# design.net
KiCad netlist of a schematic drawn in Altium Designer
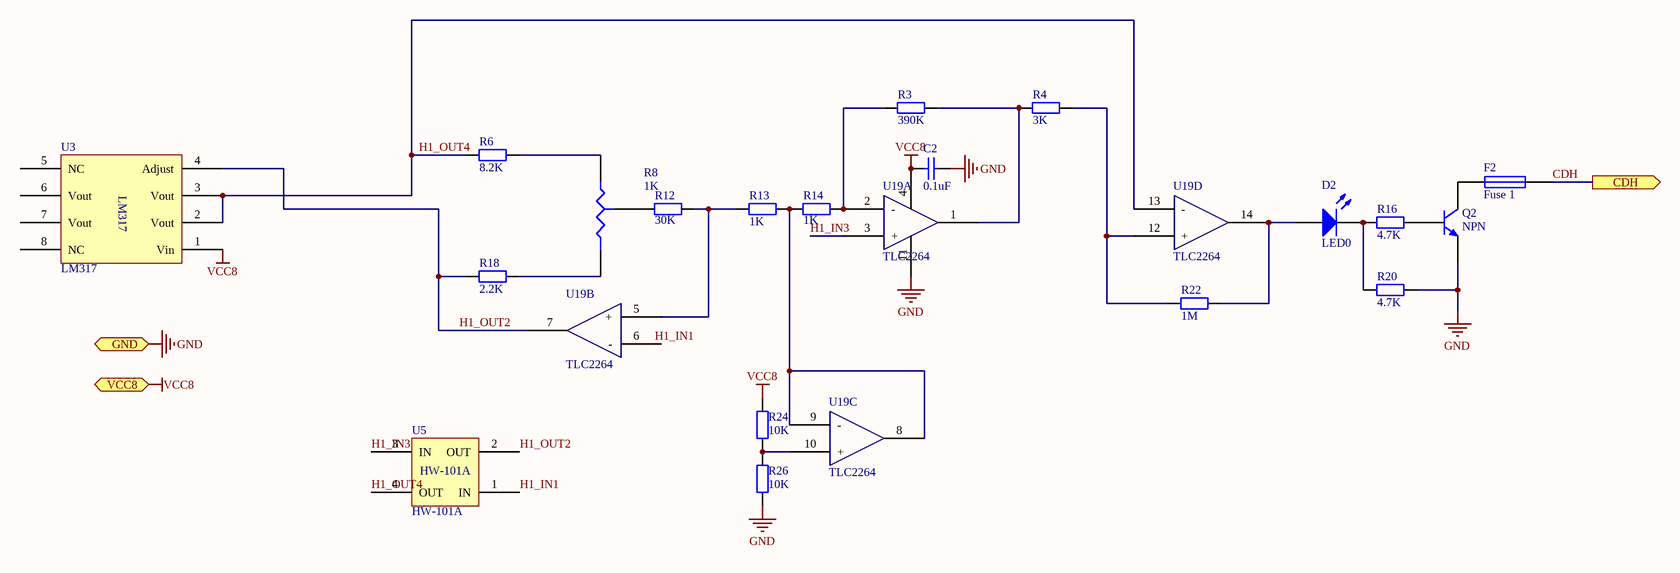
[diagram p0: 单路.SchDoc]

(export (version "E")
  (design (tool "Eeschema 10.0.6"))
  (components
    (comp (ref "C2")
      (value "0.1uF")
      (footprint "C0805")
      (description "Capacitor (Semiconductor SIM Model)")
      (fields (field (name "Comment") "Cap Semi") (field (name "PUBLISHER") "Altium Limited"))
      (libsource (lib "Miscellaneous Devices") (part "Cap Semi"))
    )
    (comp (ref "D2")
      (value "LED0")
      (footprint "LED1")
      (description "Typical INFRARED GaAs LED")
      (fields (field (name "PUBLISHER") "Altium Limited"))
      (libsource (lib "Miscellaneous Devices") (part "LED0"))
    )
    (comp (ref "F2")
      (value "Fuse 1")
      (footprint "1206")
      (description "Fuse")
      (fields (field (name "PUBLISHER") "Altium Limited"))
      (libsource (lib "Miscellaneous Devices") (part "Fuse 1"))
    )
    (comp (ref "Q2")
      (value "NPN")
      (footprint "SOT-23")
      (description "NPN Bipolar Transistor")
      (fields (field (name "PUBLISHER") "Altium Limited"))
      (libsource (lib "Miscellaneous Devices") (part "NPN"))
    )
    (comp (ref "R3")
      (value "390K")
      (footprint "0805")
      (description "Resistor")
      (fields (field (name "Comment") "Res2") (field (name "PUBLISHER") "Altium Limited"))
      (libsource (lib "Miscellaneous Devices") (part "Res2"))
    )
    (comp (ref "R4")
      (value "3K")
      (footprint "0805")
      (description "Resistor")
      (fields (field (name "Comment") "Res2") (field (name "PUBLISHER") "Altium Limited"))
      (libsource (lib "Miscellaneous Devices") (part "Res2"))
    )
    (comp (ref "R6")
      (value "8.2K")
      (footprint "0805")
      (description "Resistor")
      (fields (field (name "Comment") "Res2") (field (name "PUBLISHER") "Altium Limited"))
      (libsource (lib "Miscellaneous Devices") (part "Res2"))
    )
    (comp (ref "R8")
      (value "1K")
      (footprint "3224W")
      (description "Tapped Resistor")
      (fields (field (name "Comment") "Res Tap") (field (name "PUBLISHER") "Altium Limited"))
      (libsource (lib "Miscellaneous Devices") (part "Res Tap"))
    )
    (comp (ref "R12")
      (value "30K")
      (footprint "0805")
      (description "Resistor")
      (fields (field (name "Comment") "Res2") (field (name "PUBLISHER") "Altium Limited"))
      (libsource (lib "Miscellaneous Devices") (part "Res2"))
    )
    (comp (ref "R13")
      (value "1K")
      (footprint "0805")
      (description "Resistor")
      (fields (field (name "Comment") "Res2") (field (name "PUBLISHER") "Altium Limited"))
      (libsource (lib "Miscellaneous Devices") (part "Res2"))
    )
    (comp (ref "R14")
      (value "1K")
      (footprint "0805")
      (description "Resistor")
      (fields (field (name "Comment") "Res2") (field (name "PUBLISHER") "Altium Limited"))
      (libsource (lib "") (part "Res2_2"))
    )
    (comp (ref "R16")
      (value "4.7K")
      (footprint "0805")
      (description "Resistor")
      (fields (field (name "Comment") "Res2") (field (name "PUBLISHER") "Altium Limited"))
      (libsource (lib "Miscellaneous Devices") (part "Res2"))
    )
    (comp (ref "R18")
      (value "2.2K")
      (footprint "0805")
      (description "Resistor")
      (fields (field (name "Comment") "Res2") (field (name "PUBLISHER") "Altium Limited"))
      (libsource (lib "Miscellaneous Devices") (part "Res2"))
    )
    (comp (ref "R20")
      (value "4.7K")
      (footprint "0805")
      (description "Resistor")
      (fields (field (name "Comment") "Res2") (field (name "PUBLISHER") "Altium Limited"))
      (libsource (lib "Miscellaneous Devices") (part "Res2"))
    )
    (comp (ref "R22")
      (value "1M")
      (footprint "0805")
      (description "Resistor")
      (fields (field (name "Comment") "Res2") (field (name "PUBLISHER") "Altium Limited"))
      (libsource (lib "Miscellaneous Devices") (part "Res2"))
    )
    (comp (ref "R24")
      (value "10K")
      (footprint "0805")
      (description "Resistor")
      (fields (field (name "Comment") "Res2") (field (name "PUBLISHER") "Altium Limited"))
      (libsource (lib "") (part "Res2_1"))
    )
    (comp (ref "R26")
      (value "10K")
      (footprint "0805")
      (description "Resistor")
      (fields (field (name "Comment") "Res2") (field (name "PUBLISHER") "Altium Limited"))
      (libsource (lib "") (part "Res2_1"))
    )
    (comp (ref "U3") (value "LM317") (footprint "SO-8") (libsource (lib "磁导航") (part "LM317")))
    (comp (ref "U5") (value "HW-101A") (footprint "SOT-23-4") (libsource (lib "磁导航") (part "HW-101A")))
    (comp (ref "U19") (value "TLC2264") (footprint "TSSOP14") (libsource (lib "EXPLORER") (part "TLC2264")))
  )
  (nets
    (net (code "1") (name "/CDH") (class "Default")
      (node (ref "F2") (pin "2") (pinfunction "2_2") (pintype "passive"))
    )
    (net (code "2") (name "/H1_IN1") (class "Default")
      (node (ref "U5") (pin "1") (pinfunction "IN_1") (pintype "passive"))
    )
    (net (code "3") (name "/H1_IN3") (class "Default")
      (node (ref "U19") (pin "3") (pinfunction "+_3") (pintype "passive"))
      (node (ref "U5") (pin "3") (pinfunction "IN_3") (pintype "passive"))
    )
    (net (code "4") (name "/H1_OUT2") (class "Default")
      (node (ref "R18") (pin "1") (pinfunction "1_1") (pintype "passive"))
      (node (ref "U19") (pin "7") (pinfunction "2OUT_7") (pintype "passive"))
      (node (ref "U3") (pin "4") (pinfunction "Adjust_4") (pintype "passive"))
      (node (ref "U5") (pin "2") (pinfunction "OUT_2") (pintype "passive"))
    )
    (net (code "5") (name "/H1_OUT4") (class "Default")
      (node (ref "R6") (pin "1") (pinfunction "1_1") (pintype "passive"))
      (node (ref "U19") (pin "13") (pinfunction "-_13") (pintype "passive"))
      (node (ref "U3") (pin "2") (pinfunction "Vout_2") (pintype "passive"))
      (node (ref "U3") (pin "3") (pinfunction "Vout_3") (pintype "passive"))
      (node (ref "U5") (pin "4") (pinfunction "OUT_4") (pintype "passive"))
    )
    (net (code "6") (name "GND") (class "Default")
      (node (ref "C2") (pin "1") (pinfunction "1_1") (pintype "passive"))
      (node (ref "Q2") (pin "3") (pinfunction "E_3") (pintype "passive"))
      (node (ref "R20") (pin "2") (pinfunction "2_2") (pintype "passive"))
      (node (ref "R26") (pin "1") (pinfunction "1_1") (pintype "passive"))
      (node (ref "U19") (pin "11") (pinfunction "GND_11") (pintype "passive"))
    )
    (net (code "7") (name "Net-(D2-A)") (class "Default")
      (node (ref "D2") (pin "1") (pinfunction "A_1") (pintype "passive"))
      (node (ref "R22") (pin "2") (pinfunction "2_2") (pintype "passive"))
      (node (ref "U19") (pin "14") (pinfunction "4OUT_14") (pintype "passive"))
    )
    (net (code "8") (name "Net-(D2-K)") (class "Default")
      (node (ref "D2") (pin "2") (pinfunction "K_2") (pintype "passive"))
      (node (ref "R16") (pin "1") (pinfunction "1_1") (pintype "passive"))
      (node (ref "R20") (pin "1") (pinfunction "1_1") (pintype "passive"))
    )
    (net (code "9") (name "Net-(Q2-B)") (class "Default")
      (node (ref "Q2") (pin "2") (pinfunction "B_2") (pintype "passive"))
      (node (ref "R16") (pin "2") (pinfunction "2_2") (pintype "passive"))
    )
    (net (code "10") (name "Net-(Q2-C)") (class "Default")
      (node (ref "F2") (pin "1") (pinfunction "1_1") (pintype "passive"))
      (node (ref "Q2") (pin "1") (pinfunction "C_1") (pintype "passive"))
    )
    (net (code "11") (name "Net-(R8-A)") (class "Default")
      (node (ref "R6") (pin "2") (pinfunction "2_2") (pintype "passive"))
      (node (ref "R8") (pin "1") (pinfunction "A_1") (pintype "passive"))
    )
    (net (code "12") (name "Net-(R8-B)") (class "Default")
      (node (ref "R18") (pin "2") (pinfunction "2_2") (pintype "passive"))
      (node (ref "R8") (pin "2") (pinfunction "B_2") (pintype "passive"))
    )
    (net (code "13") (name "Net-(R8-TAP)") (class "Default")
      (node (ref "R12") (pin "1") (pinfunction "1_1") (pintype "passive"))
      (node (ref "R8") (pin "3") (pinfunction "TAP_3") (pintype "passive"))
    )
    (net (code "14") (name "Net-(U19A--)") (class "Default")
      (node (ref "R14") (pin "1") (pinfunction "1_1") (pintype "passive"))
      (node (ref "R3") (pin "1") (pinfunction "1_1") (pintype "passive"))
      (node (ref "U19") (pin "2") (pinfunction "-_2") (pintype "passive"))
    )
    (net (code "15") (name "Net-(U19A-1OUT)") (class "Default")
      (node (ref "R3") (pin "2") (pinfunction "2_2") (pintype "passive"))
      (node (ref "R4") (pin "1") (pinfunction "1_1") (pintype "passive"))
      (node (ref "U19") (pin "1") (pinfunction "1OUT_1") (pintype "passive"))
    )
    (net (code "16") (name "Net-(U19B-+)") (class "Default")
      (node (ref "R12") (pin "2") (pinfunction "2_2") (pintype "passive"))
      (node (ref "R13") (pin "1") (pinfunction "1_1") (pintype "passive"))
      (node (ref "U19") (pin "5") (pinfunction "+_5") (pintype "passive"))
    )
    (net (code "17") (name "Net-(U19C-+)") (class "Default")
      (node (ref "R24") (pin "1") (pinfunction "1_1") (pintype "passive"))
      (node (ref "R26") (pin "2") (pinfunction "2_2") (pintype "passive"))
      (node (ref "U19") (pin "10") (pinfunction "+_10") (pintype "passive"))
    )
    (net (code "18") (name "Net-(U19C--)") (class "Default")
      (node (ref "R13") (pin "2") (pinfunction "2_2") (pintype "passive"))
      (node (ref "R14") (pin "2") (pinfunction "2_2") (pintype "passive"))
      (node (ref "U19") (pin "8") (pinfunction "3OUT_8") (pintype "passive"))
      (node (ref "U19") (pin "9") (pinfunction "-_9") (pintype "passive"))
    )
    (net (code "19") (name "Net-(U19D-+)") (class "Default")
      (node (ref "R22") (pin "1") (pinfunction "1_1") (pintype "passive"))
      (node (ref "R4") (pin "2") (pinfunction "2_2") (pintype "passive"))
      (node (ref "U19") (pin "12") (pinfunction "+_12") (pintype "passive"))
    )
    (net (code "20") (name "VCC8") (class "Default")
      (node (ref "C2") (pin "2") (pinfunction "2_2") (pintype "passive"))
      (node (ref "R24") (pin "2") (pinfunction "2_2") (pintype "passive"))
      (node (ref "U19") (pin "4") (pinfunction "VCC_4") (pintype "passive"))
      (node (ref "U3") (pin "1") (pinfunction "Vin_1") (pintype "passive"))
    )
    (net (code "21") (name "unconnected-(U3-NC-Pad5)") (class "Default")
      (node (ref "U3") (pin "5") (pinfunction "NC_5") (pintype "passive"))
    )
    (net (code "22") (name "unconnected-(U3-NC-Pad8)") (class "Default")
      (node (ref "U3") (pin "8") (pinfunction "NC_8") (pintype "passive"))
    )
    (net (code "23") (name "unconnected-(U3-Vout-Pad6)") (class "Default")
      (node (ref "U3") (pin "6") (pinfunction "Vout_6") (pintype "passive"))
    )
    (net (code "24") (name "unconnected-(U3-Vout-Pad7)") (class "Default")
      (node (ref "U3") (pin "7") (pinfunction "Vout_7") (pintype "passive"))
    )
    (net (code "25") (name "unconnected-(U19B---Pad6)") (class "Default")
      (node (ref "U19") (pin "6") (pinfunction "-_6") (pintype "passive"))
    )
  )
)
